# untitled.net
KiCad netlist of a schematic drawn in EAGLE
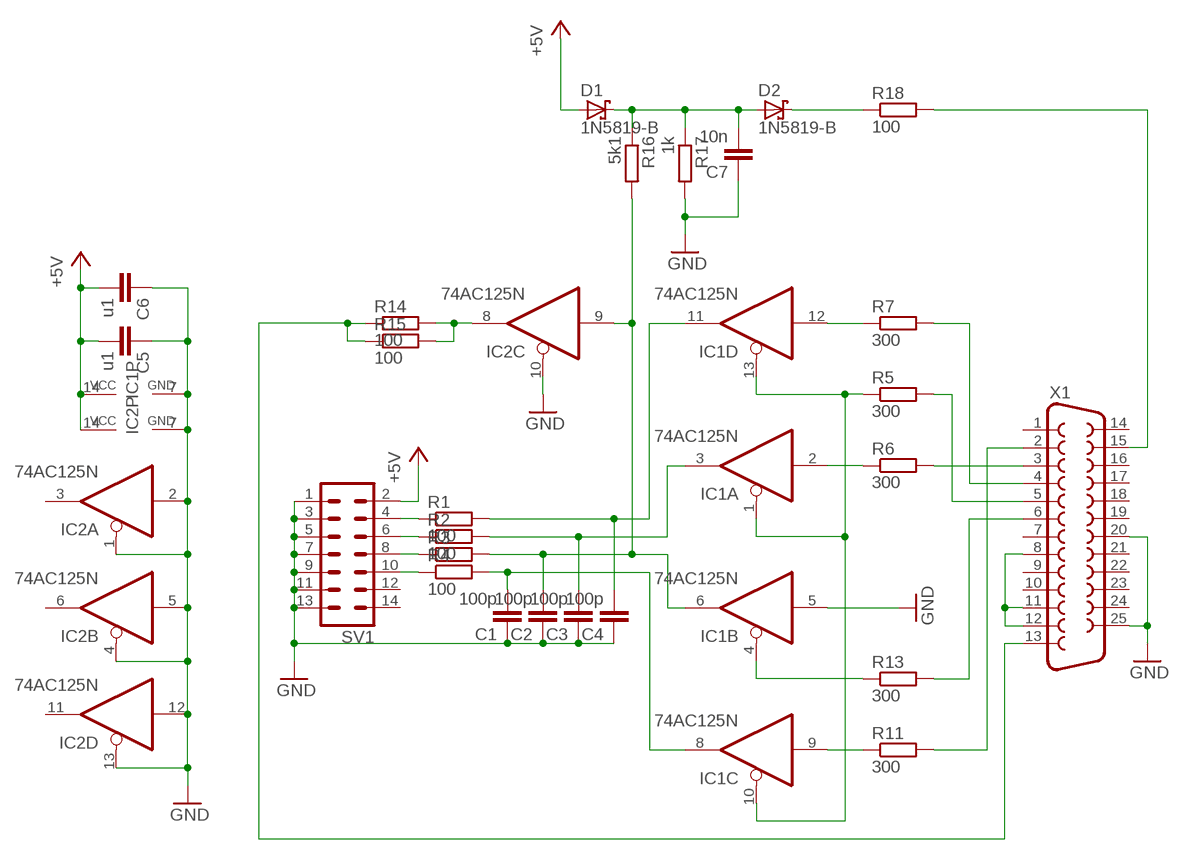
[diagram p0: schematic, sheet 1]

(export (version "E")
  (design (tool "Eeschema 10.0.6"))
  (components
    (comp (ref "C1")
      (value "100p")
      (footprint "eagle-import:C025-025X050")
      (libsource (lib "eagle-import") (part "C-EU025-025X050"))
    )
    (comp (ref "C2")
      (value "100p")
      (footprint "eagle-import:C025-025X050")
      (libsource (lib "eagle-import") (part "C-EU025-025X050"))
    )
    (comp (ref "C3")
      (value "100p")
      (footprint "eagle-import:C025-025X050")
      (libsource (lib "eagle-import") (part "C-EU025-025X050"))
    )
    (comp (ref "C4")
      (value "100p")
      (footprint "eagle-import:C025-025X050")
      (libsource (lib "eagle-import") (part "C-EU025-025X050"))
    )
    (comp (ref "C5")
      (value "u1")
      (footprint "eagle-import:C025-025X050")
      (libsource (lib "eagle-import") (part "C-EU025-025X050"))
    )
    (comp (ref "C6")
      (value "u1")
      (footprint "eagle-import:C025-025X050")
      (libsource (lib "eagle-import") (part "C-EU025-025X050"))
    )
    (comp (ref "C7")
      (value "10n")
      (footprint "eagle-import:C025-025X050")
      (libsource (lib "eagle-import") (part "C-EU025-025X050"))
    )
    (comp (ref "D1")
      (value "1N5819-B")
      (footprint "eagle-import:DO41-7.6")
      (libsource (lib "eagle-import") (part "1N5819-B"))
    )
    (comp (ref "D2")
      (value "1N5819-B")
      (footprint "eagle-import:DO41-7.6")
      (libsource (lib "eagle-import") (part "1N5819-B"))
    )
    (comp (ref "IC1")
      (value "74AC125N")
      (footprint "eagle-import:DIL14")
      (libsource (lib "eagle-import") (part "74125NAC"))
    )
    (comp (ref "IC2")
      (value "74AC125N")
      (footprint "eagle-import:DIL14")
      (libsource (lib "eagle-import") (part "74125NAC"))
    )
    (comp (ref "R1")
      (value "100")
      (footprint "eagle-import:0207_2V")
      (libsource (lib "eagle-import") (part "R-EU_0207/2V"))
    )
    (comp (ref "R2")
      (value "100")
      (footprint "eagle-import:0207_2V")
      (libsource (lib "eagle-import") (part "R-EU_0207/2V"))
    )
    (comp (ref "R3")
      (value "R-EU_0207/2V")
      (footprint "eagle-import:0207_2V")
      (libsource (lib "eagle-import") (part "R-EU_0207/2V"))
    )
    (comp (ref "R4")
      (value "100")
      (footprint "eagle-import:0207_2V")
      (libsource (lib "eagle-import") (part "R-EU_0207/2V"))
    )
    (comp (ref "R5")
      (value "300")
      (footprint "eagle-import:0207_7")
      (libsource (lib "eagle-import") (part "R-EU_0207/7"))
    )
    (comp (ref "R6")
      (value "300")
      (footprint "eagle-import:0207_7")
      (libsource (lib "eagle-import") (part "R-EU_0207/7"))
    )
    (comp (ref "R7")
      (value "300")
      (footprint "eagle-import:0207_7")
      (libsource (lib "eagle-import") (part "R-EU_0207/7"))
    )
    (comp (ref "R11")
      (value "300")
      (footprint "eagle-import:0207_12")
      (libsource (lib "eagle-import") (part "R-EU_0207/12"))
    )
    (comp (ref "R13")
      (value "300")
      (footprint "eagle-import:0207_7")
      (libsource (lib "eagle-import") (part "R-EU_0207/7"))
    )
    (comp (ref "R14")
      (value "100")
      (footprint "eagle-import:0207_7")
      (libsource (lib "eagle-import") (part "R-EU_0207/7"))
    )
    (comp (ref "R15")
      (value "100")
      (footprint "eagle-import:0207_7")
      (libsource (lib "eagle-import") (part "R-EU_0207/7"))
    )
    (comp (ref "R16")
      (value "5k1")
      (footprint "eagle-import:0309_12")
      (libsource (lib "eagle-import") (part "R-EU_0309/12"))
    )
    (comp (ref "R17")
      (value "1k")
      (footprint "eagle-import:0207_7")
      (libsource (lib "eagle-import") (part "R-EU_0207/7"))
    )
    (comp (ref "R18")
      (value "100")
      (footprint "eagle-import:0207_2V")
      (libsource (lib "eagle-import") (part "R-EU_0207/2V"))
    )
    (comp (ref "SV1")
      (value "ML14")
      (footprint "eagle-import:ML14")
      (libsource (lib "eagle-import") (part "ML14"))
    )
    (comp (ref "X1")
      (value "F25HP")
      (footprint "eagle-import:F25HP")
      (libsource (lib "eagle-import") (part "F25HP"))
    )
  )
  (nets
    (net (code "1") (name "+5V") (class "Default")
      (node (ref "C5") (pin "2") (pinfunction "2_2") (pintype "passive"))
      (node (ref "C6") (pin "2") (pinfunction "2_2") (pintype "passive"))
      (node (ref "D1") (pin "A") (pinfunction "A_A") (pintype "passive"))
      (node (ref "IC1") (pin "14") (pinfunction "VCC_14") (pintype "power_in"))
      (node (ref "IC2") (pin "14") (pinfunction "VCC_14") (pintype "power_in"))
      (node (ref "SV1") (pin "2") (pinfunction "2_2") (pintype "passive"))
    )
    (net (code "2") (name "GND") (class "Default")
      (node (ref "C1") (pin "1") (pinfunction "1_1") (pintype "passive"))
      (node (ref "C2") (pin "1") (pinfunction "1_1") (pintype "passive"))
      (node (ref "C3") (pin "1") (pinfunction "1_1") (pintype "passive"))
      (node (ref "C4") (pin "1") (pinfunction "1_1") (pintype "passive"))
      (node (ref "C5") (pin "1") (pinfunction "1_1") (pintype "passive"))
      (node (ref "C6") (pin "1") (pinfunction "1_1") (pintype "passive"))
      (node (ref "C7") (pin "1") (pinfunction "1_1") (pintype "passive"))
      (node (ref "IC1") (pin "5") (pinfunction "I_5") (pintype "input"))
      (node (ref "IC1") (pin "7") (pinfunction "GND_7") (pintype "power_in"))
      (node (ref "IC2") (pin "1") (pinfunction "OE_1") (pintype "input"))
      (node (ref "IC2") (pin "10") (pinfunction "OE_10") (pintype "input"))
      (node (ref "IC2") (pin "12") (pinfunction "I_12") (pintype "input"))
      (node (ref "IC2") (pin "13") (pinfunction "OE_13") (pintype "input"))
      (node (ref "IC2") (pin "2") (pinfunction "I_2") (pintype "input"))
      (node (ref "IC2") (pin "4") (pinfunction "OE_4") (pintype "input"))
      (node (ref "IC2") (pin "5") (pinfunction "I_5") (pintype "input"))
      (node (ref "IC2") (pin "7") (pinfunction "GND_7") (pintype "power_in"))
      (node (ref "R17") (pin "2") (pinfunction "2_2") (pintype "passive"))
      (node (ref "SV1") (pin "1") (pinfunction "1_1") (pintype "passive"))
      (node (ref "SV1") (pin "11") (pinfunction "11_11") (pintype "passive"))
      (node (ref "SV1") (pin "13") (pinfunction "13_13") (pintype "passive"))
      (node (ref "SV1") (pin "3") (pinfunction "3_3") (pintype "passive"))
      (node (ref "SV1") (pin "5") (pinfunction "5_5") (pintype "passive"))
      (node (ref "SV1") (pin "7") (pinfunction "7_7") (pintype "passive"))
      (node (ref "SV1") (pin "9") (pinfunction "9_9") (pintype "passive"))
      (node (ref "X1") (pin "20") (pinfunction "20_20") (pintype "passive"))
      (node (ref "X1") (pin "25") (pinfunction "25_25") (pintype "passive"))
    )
    (net (code "3") (name "Net-(C7-Pad2)") (class "Default")
      (node (ref "C7") (pin "2") (pinfunction "2_2") (pintype "passive"))
      (node (ref "D1") (pin "C") (pinfunction "C_C") (pintype "passive"))
      (node (ref "D2") (pin "A") (pinfunction "A_A") (pintype "passive"))
      (node (ref "R16") (pin "1") (pinfunction "1_1") (pintype "passive"))
      (node (ref "R17") (pin "1") (pinfunction "1_1") (pintype "passive"))
    )
    (net (code "4") (name "Net-(D2-PadC)") (class "Default")
      (node (ref "D2") (pin "C") (pinfunction "C_C") (pintype "passive"))
      (node (ref "R18") (pin "1") (pinfunction "1_1") (pintype "passive"))
    )
    (net (code "5") (name "Net-(IC1A-I)") (class "Default")
      (node (ref "IC1") (pin "2") (pinfunction "I_2") (pintype "input"))
      (node (ref "R6") (pin "1") (pinfunction "1_1") (pintype "passive"))
    )
    (net (code "6") (name "Net-(IC1A-O)") (class "Default")
      (node (ref "C3") (pin "2") (pinfunction "2_2") (pintype "passive"))
      (node (ref "IC1") (pin "3") (pinfunction "O_3") (pintype "tri_state"))
      (node (ref "R2") (pin "2") (pinfunction "2_2") (pintype "passive"))
    )
    (net (code "7") (name "Net-(IC1A-OE)") (class "Default")
      (node (ref "IC1") (pin "1") (pinfunction "OE_1") (pintype "input"))
      (node (ref "IC1") (pin "10") (pinfunction "OE_10") (pintype "input"))
      (node (ref "IC1") (pin "13") (pinfunction "OE_13") (pintype "input"))
      (node (ref "R5") (pin "1") (pinfunction "1_1") (pintype "passive"))
    )
    (net (code "8") (name "Net-(IC1B-O)") (class "Default")
      (node (ref "C2") (pin "2") (pinfunction "2_2") (pintype "passive"))
      (node (ref "IC1") (pin "6") (pinfunction "O_6") (pintype "tri_state"))
      (node (ref "IC2") (pin "9") (pinfunction "I_9") (pintype "input"))
      (node (ref "R16") (pin "2") (pinfunction "2_2") (pintype "passive"))
      (node (ref "R3") (pin "2") (pinfunction "2_2") (pintype "passive"))
    )
    (net (code "9") (name "Net-(IC1B-OE)") (class "Default")
      (node (ref "IC1") (pin "4") (pinfunction "OE_4") (pintype "input"))
      (node (ref "R13") (pin "1") (pinfunction "1_1") (pintype "passive"))
    )
    (net (code "10") (name "Net-(IC1C-I)") (class "Default")
      (node (ref "IC1") (pin "9") (pinfunction "I_9") (pintype "input"))
      (node (ref "R11") (pin "1") (pinfunction "1_1") (pintype "passive"))
    )
    (net (code "11") (name "Net-(IC1C-O)") (class "Default")
      (node (ref "C1") (pin "2") (pinfunction "2_2") (pintype "passive"))
      (node (ref "IC1") (pin "8") (pinfunction "O_8") (pintype "tri_state"))
      (node (ref "R4") (pin "2") (pinfunction "2_2") (pintype "passive"))
    )
    (net (code "12") (name "Net-(IC1D-I)") (class "Default")
      (node (ref "IC1") (pin "12") (pinfunction "I_12") (pintype "input"))
      (node (ref "R7") (pin "1") (pinfunction "1_1") (pintype "passive"))
    )
    (net (code "13") (name "Net-(IC1D-O)") (class "Default")
      (node (ref "C4") (pin "2") (pinfunction "2_2") (pintype "passive"))
      (node (ref "IC1") (pin "11") (pinfunction "O_11") (pintype "tri_state"))
      (node (ref "R1") (pin "2") (pinfunction "2_2") (pintype "passive"))
    )
    (net (code "14") (name "Net-(IC2C-O)") (class "Default")
      (node (ref "IC2") (pin "8") (pinfunction "O_8") (pintype "tri_state"))
      (node (ref "R14") (pin "2") (pinfunction "2_2") (pintype "passive"))
      (node (ref "R15") (pin "2") (pinfunction "2_2") (pintype "passive"))
    )
    (net (code "15") (name "Net-(R1-Pad1)") (class "Default")
      (node (ref "R1") (pin "1") (pinfunction "1_1") (pintype "passive"))
      (node (ref "SV1") (pin "4") (pinfunction "4_4") (pintype "passive"))
    )
    (net (code "16") (name "Net-(R2-Pad1)") (class "Default")
      (node (ref "R2") (pin "1") (pinfunction "1_1") (pintype "passive"))
      (node (ref "SV1") (pin "6") (pinfunction "6_6") (pintype "passive"))
    )
    (net (code "17") (name "Net-(R3-Pad1)") (class "Default")
      (node (ref "R3") (pin "1") (pinfunction "1_1") (pintype "passive"))
      (node (ref "SV1") (pin "8") (pinfunction "8_8") (pintype "passive"))
    )
    (net (code "18") (name "Net-(R4-Pad1)") (class "Default")
      (node (ref "R4") (pin "1") (pinfunction "1_1") (pintype "passive"))
      (node (ref "SV1") (pin "10") (pinfunction "10_10") (pintype "passive"))
    )
    (net (code "19") (name "Net-(R5-Pad2)") (class "Default")
      (node (ref "R5") (pin "2") (pinfunction "2_2") (pintype "passive"))
      (node (ref "X1") (pin "5") (pinfunction "5_5") (pintype "passive"))
    )
    (net (code "20") (name "Net-(R6-Pad2)") (class "Default")
      (node (ref "R6") (pin "2") (pinfunction "2_2") (pintype "passive"))
      (node (ref "X1") (pin "3") (pinfunction "3_3") (pintype "passive"))
    )
    (net (code "21") (name "Net-(R7-Pad2)") (class "Default")
      (node (ref "R7") (pin "2") (pinfunction "2_2") (pintype "passive"))
      (node (ref "X1") (pin "4") (pinfunction "4_4") (pintype "passive"))
    )
    (net (code "22") (name "Net-(R11-Pad2)") (class "Default")
      (node (ref "R11") (pin "2") (pinfunction "2_2") (pintype "passive"))
      (node (ref "X1") (pin "2") (pinfunction "2_2") (pintype "passive"))
    )
    (net (code "23") (name "Net-(R13-Pad2)") (class "Default")
      (node (ref "R13") (pin "2") (pinfunction "2_2") (pintype "passive"))
      (node (ref "X1") (pin "6") (pinfunction "6_6") (pintype "passive"))
    )
    (net (code "24") (name "Net-(R14-Pad1)") (class "Default")
      (node (ref "R14") (pin "1") (pinfunction "1_1") (pintype "passive"))
      (node (ref "R15") (pin "1") (pinfunction "1_1") (pintype "passive"))
      (node (ref "X1") (pin "13") (pinfunction "13_13") (pintype "passive"))
    )
    (net (code "25") (name "Net-(R18-Pad2)") (class "Default")
      (node (ref "R18") (pin "2") (pinfunction "2_2") (pintype "passive"))
      (node (ref "X1") (pin "15") (pinfunction "15_15") (pintype "passive"))
    )
    (net (code "26") (name "Net-(X1-Pad11)") (class "Default")
      (node (ref "X1") (pin "11") (pinfunction "11_11") (pintype "passive"))
      (node (ref "X1") (pin "12") (pinfunction "12_12") (pintype "passive"))
      (node (ref "X1") (pin "8") (pinfunction "8_8") (pintype "passive"))
    )
    (net (code "27") (name "unconnected-(IC2A-O-Pad3)") (class "Default")
      (node (ref "IC2") (pin "3") (pinfunction "O_3") (pintype "tri_state"))
    )
    (net (code "28") (name "unconnected-(IC2B-O-Pad6)") (class "Default")
      (node (ref "IC2") (pin "6") (pinfunction "O_6") (pintype "tri_state"))
    )
    (net (code "29") (name "unconnected-(IC2D-O-Pad11)") (class "Default")
      (node (ref "IC2") (pin "11") (pinfunction "O_11") (pintype "tri_state"))
    )
    (net (code "30") (name "unconnected-(SV1-Pad12)") (class "Default")
      (node (ref "SV1") (pin "12") (pinfunction "12_12") (pintype "passive"))
    )
    (net (code "31") (name "unconnected-(SV1-Pad14)") (class "Default")
      (node (ref "SV1") (pin "14") (pinfunction "14_14") (pintype "passive"))
    )
    (net (code "32") (name "unconnected-(X1-Pad1)") (class "Default")
      (node (ref "X1") (pin "1") (pinfunction "1_1") (pintype "passive"))
    )
    (net (code "33") (name "unconnected-(X1-Pad7)") (class "Default")
      (node (ref "X1") (pin "7") (pinfunction "7_7") (pintype "passive"))
    )
    (net (code "34") (name "unconnected-(X1-Pad9)") (class "Default")
      (node (ref "X1") (pin "9") (pinfunction "9_9") (pintype "passive"))
    )
    (net (code "35") (name "unconnected-(X1-Pad10)") (class "Default")
      (node (ref "X1") (pin "10") (pinfunction "10_10") (pintype "passive"))
    )
    (net (code "36") (name "unconnected-(X1-Pad14)") (class "Default")
      (node (ref "X1") (pin "14") (pinfunction "14_14") (pintype "passive"))
    )
    (net (code "37") (name "unconnected-(X1-Pad16)") (class "Default")
      (node (ref "X1") (pin "16") (pinfunction "16_16") (pintype "passive"))
    )
    (net (code "38") (name "unconnected-(X1-Pad17)") (class "Default")
      (node (ref "X1") (pin "17") (pinfunction "17_17") (pintype "passive"))
    )
    (net (code "39") (name "unconnected-(X1-Pad18)") (class "Default")
      (node (ref "X1") (pin "18") (pinfunction "18_18") (pintype "passive"))
    )
    (net (code "40") (name "unconnected-(X1-Pad19)") (class "Default")
      (node (ref "X1") (pin "19") (pinfunction "19_19") (pintype "passive"))
    )
    (net (code "41") (name "unconnected-(X1-Pad21)") (class "Default")
      (node (ref "X1") (pin "21") (pinfunction "21_21") (pintype "passive"))
    )
    (net (code "42") (name "unconnected-(X1-Pad22)") (class "Default")
      (node (ref "X1") (pin "22") (pinfunction "22_22") (pintype "passive"))
    )
    (net (code "43") (name "unconnected-(X1-Pad23)") (class "Default")
      (node (ref "X1") (pin "23") (pinfunction "23_23") (pintype "passive"))
    )
    (net (code "44") (name "unconnected-(X1-Pad24)") (class "Default")
      (node (ref "X1") (pin "24") (pinfunction "24_24") (pintype "passive"))
    )
  )
)
